# 1206_array.net
KiCad netlist of a schematic drawn in Altium Designer
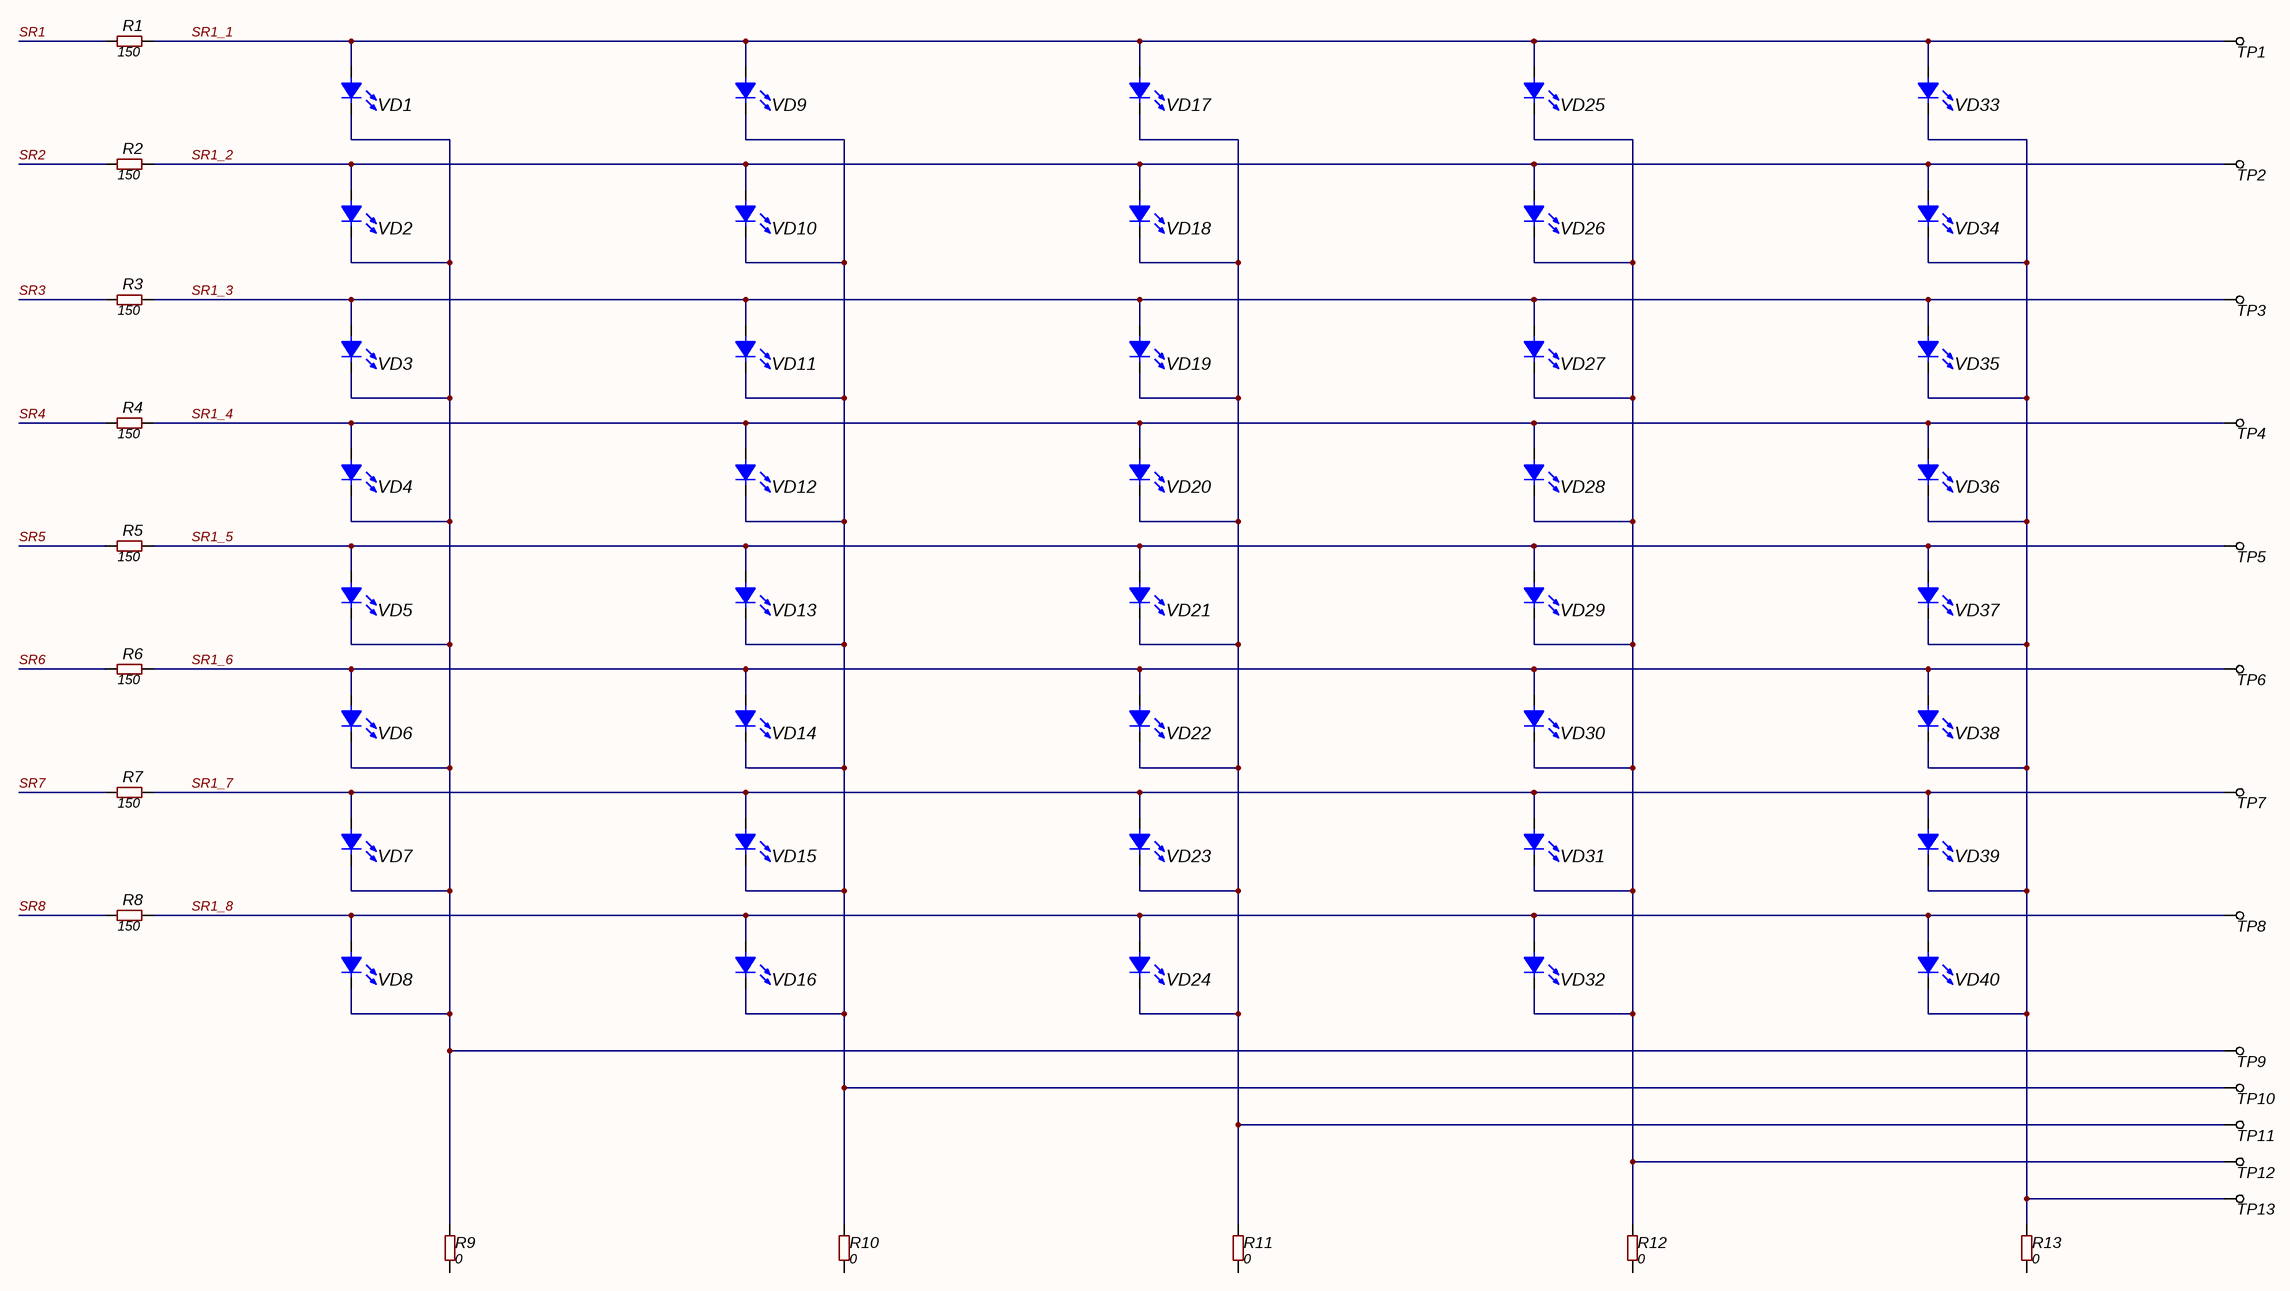
[diagram p0: 1206_array.SchDoc]

(export (version "E")
  (design (tool "Eeschema 10.0.6"))
  (components
    (comp (ref "R1")
      (value "150")
      (footprint "RES: 0603")
      (fields
        (field (name "MANUFACTURER") "Yageo")
        (field (name "PARTNUMBER") "RC0603JR-07100RL")
        (field (name "VALUEMANUFACTURERPARTNUMBER") "Resistor film, 150, , 0603, 0.1W, -55...+125°C")
      )
      (libsource (lib "") (part "Resistor_0603_1"))
    )
    (comp (ref "R2")
      (value "150")
      (footprint "RES: 0603")
      (fields
        (field (name "MANUFACTURER") "Yageo")
        (field (name "PARTNUMBER") "RC0603JR-07100RL")
        (field (name "VALUEMANUFACTURERPARTNUMBER") "Resistor film, 150, , 0603, 0.1W, -55...+125°C")
      )
      (libsource (lib "") (part "Resistor_0603_1"))
    )
    (comp (ref "R3")
      (value "150")
      (footprint "RES: 0603")
      (fields
        (field (name "MANUFACTURER") "Yageo")
        (field (name "PARTNUMBER") "RC0603JR-07100RL")
        (field (name "VALUEMANUFACTURERPARTNUMBER") "Resistor film, 150, , 0603, 0.1W, -55...+125°C")
      )
      (libsource (lib "") (part "Resistor_0603_1"))
    )
    (comp (ref "R4")
      (value "150")
      (footprint "RES: 0603")
      (fields
        (field (name "MANUFACTURER") "Yageo")
        (field (name "PARTNUMBER") "RC0603JR-07100RL")
        (field (name "VALUEMANUFACTURERPARTNUMBER") "Resistor film, 150, , 0603, 0.1W, -55...+125°C")
      )
      (libsource (lib "") (part "Resistor_0603_1"))
    )
    (comp (ref "R5")
      (value "150")
      (footprint "RES: 0603")
      (fields
        (field (name "MANUFACTURER") "Yageo")
        (field (name "PARTNUMBER") "RC0603JR-07100RL")
        (field (name "VALUEMANUFACTURERPARTNUMBER") "Resistor film, 150, , 0603, 0.1W, -55...+125°C")
      )
      (libsource (lib "") (part "Resistor_0603_1"))
    )
    (comp (ref "R6")
      (value "150")
      (footprint "RES: 0603")
      (fields
        (field (name "MANUFACTURER") "Yageo")
        (field (name "PARTNUMBER") "RC0603JR-07100RL")
        (field (name "VALUEMANUFACTURERPARTNUMBER") "Resistor film, 150, , 0603, 0.1W, -55...+125°C")
      )
      (libsource (lib "") (part "Resistor_0603_1"))
    )
    (comp (ref "R7")
      (value "150")
      (footprint "RES: 0603")
      (fields
        (field (name "MANUFACTURER") "Yageo")
        (field (name "PARTNUMBER") "RC0603JR-07100RL")
        (field (name "VALUEMANUFACTURERPARTNUMBER") "Resistor film, 150, , 0603, 0.1W, -55...+125°C")
      )
      (libsource (lib "") (part "Resistor_0603_1"))
    )
    (comp (ref "R8")
      (value "150")
      (footprint "RES: 0603")
      (fields
        (field (name "MANUFACTURER") "Yageo")
        (field (name "PARTNUMBER") "RC0603JR-07100RL")
        (field (name "VALUEMANUFACTURERPARTNUMBER") "Resistor film, 150, , 0603, 0.1W, -55...+125°C")
      )
      (libsource (lib "") (part "Resistor_0603_1"))
    )
    (comp (ref "R9")
      (value "0")
      (footprint "RES: 0603")
      (fields
        (field (name "MANUFACTURER") "Yageo")
        (field (name "PARTNUMBER") "RC0603JR-07100RL")
        (field (name "VALUEMANUFACTURERPARTNUMBER") "Resistor film, 0, , 0603, 0.1W, -55...+125°C")
      )
      (libsource (lib "resistor") (part "Resistor_0603"))
    )
    (comp (ref "R10")
      (value "0")
      (footprint "RES: 0603")
      (fields
        (field (name "MANUFACTURER") "Yageo")
        (field (name "PARTNUMBER") "RC0603JR-07100RL")
        (field (name "VALUEMANUFACTURERPARTNUMBER") "Resistor film, 0, , 0603, 0.1W, -55...+125°C")
      )
      (libsource (lib "resistor") (part "Resistor_0603"))
    )
    (comp (ref "R11")
      (value "0")
      (footprint "RES: 0603")
      (fields
        (field (name "MANUFACTURER") "Yageo")
        (field (name "PARTNUMBER") "RC0603JR-07100RL")
        (field (name "VALUEMANUFACTURERPARTNUMBER") "Resistor film, 0, , 0603, 0.1W, -55...+125°C")
      )
      (libsource (lib "resistor") (part "Resistor_0603"))
    )
    (comp (ref "R12")
      (value "0")
      (footprint "RES: 0603")
      (fields
        (field (name "MANUFACTURER") "Yageo")
        (field (name "PARTNUMBER") "RC0603JR-07100RL")
        (field (name "VALUEMANUFACTURERPARTNUMBER") "Resistor film, 0, , 0603, 0.1W, -55...+125°C")
      )
      (libsource (lib "resistor") (part "Resistor_0603"))
    )
    (comp (ref "R13")
      (value "0")
      (footprint "RES: 0603")
      (fields
        (field (name "MANUFACTURER") "Yageo")
        (field (name "PARTNUMBER") "RC0603JR-07100RL")
        (field (name "VALUEMANUFACTURERPARTNUMBER") "Resistor film, 0, , 0603, 0.1W, -55...+125°C")
      )
      (libsource (lib "resistor") (part "Resistor_0603"))
    )
    (comp (ref "TP1")
      (value "Testpoint_HS1mm")
      (footprint "TestPoint(without 3D)")
      (libsource (lib "connector") (part "Testpoint_HS1mm"))
    )
    (comp (ref "TP2")
      (value "Testpoint_HS1mm")
      (footprint "TestPoint(without 3D)")
      (libsource (lib "connector") (part "Testpoint_HS1mm"))
    )
    (comp (ref "TP3")
      (value "Testpoint_HS1mm")
      (footprint "TestPoint(without 3D)")
      (libsource (lib "connector") (part "Testpoint_HS1mm"))
    )
    (comp (ref "TP4")
      (value "Testpoint_HS1mm")
      (footprint "TestPoint(without 3D)")
      (libsource (lib "connector") (part "Testpoint_HS1mm"))
    )
    (comp (ref "TP5")
      (value "Testpoint_HS1mm")
      (footprint "TestPoint(without 3D)")
      (libsource (lib "connector") (part "Testpoint_HS1mm"))
    )
    (comp (ref "TP6")
      (value "Testpoint_HS1mm")
      (footprint "TestPoint(without 3D)")
      (libsource (lib "connector") (part "Testpoint_HS1mm"))
    )
    (comp (ref "TP7")
      (value "Testpoint_HS1mm")
      (footprint "TestPoint(without 3D)")
      (libsource (lib "connector") (part "Testpoint_HS1mm"))
    )
    (comp (ref "TP8")
      (value "Testpoint_HS1mm")
      (footprint "TestPoint(without 3D)")
      (libsource (lib "connector") (part "Testpoint_HS1mm"))
    )
    (comp (ref "TP9")
      (value "Testpoint_HS1mm")
      (footprint "TestPoint(without 3D)")
      (libsource (lib "connector") (part "Testpoint_HS1mm"))
    )
    (comp (ref "TP10")
      (value "Testpoint_HS1mm")
      (footprint "TestPoint(without 3D)")
      (libsource (lib "connector") (part "Testpoint_HS1mm"))
    )
    (comp (ref "TP11")
      (value "Testpoint_HS1mm")
      (footprint "TestPoint(without 3D)")
      (libsource (lib "connector") (part "Testpoint_HS1mm"))
    )
    (comp (ref "TP12")
      (value "Testpoint_HS1mm")
      (footprint "TestPoint(without 3D)")
      (libsource (lib "connector") (part "Testpoint_HS1mm"))
    )
    (comp (ref "TP13")
      (value "Testpoint_HS1mm")
      (footprint "TestPoint(without 3D)")
      (libsource (lib "connector") (part "Testpoint_HS1mm"))
    )
    (comp (ref "VD1")
      (value "~")
      (footprint "LED: 1206Y")
      (fields (field (name "VALUEMANUFACTURERPARTNUMBER") "LED, Green, *, *, *, -55...+150°C"))
      (libsource (lib "diode") (part "LED_single"))
    )
    (comp (ref "VD2")
      (value "~")
      (footprint "LED: 1206Y")
      (fields (field (name "VALUEMANUFACTURERPARTNUMBER") "LED, Green, *, *, *, -55...+150°C"))
      (libsource (lib "diode") (part "LED_single"))
    )
    (comp (ref "VD3")
      (value "~")
      (footprint "LED: 1206Y")
      (fields (field (name "VALUEMANUFACTURERPARTNUMBER") "LED, Green, *, *, *, -55...+150°C"))
      (libsource (lib "diode") (part "LED_single"))
    )
    (comp (ref "VD4")
      (value "~")
      (footprint "LED: 1206Y")
      (fields (field (name "VALUEMANUFACTURERPARTNUMBER") "LED, Green, *, *, *, -55...+150°C"))
      (libsource (lib "diode") (part "LED_single"))
    )
    (comp (ref "VD5")
      (value "~")
      (footprint "LED: 1206Y")
      (fields (field (name "VALUEMANUFACTURERPARTNUMBER") "LED, Green, *, *, *, -55...+150°C"))
      (libsource (lib "diode") (part "LED_single"))
    )
    (comp (ref "VD6")
      (value "~")
      (footprint "LED: 1206Y")
      (fields (field (name "VALUEMANUFACTURERPARTNUMBER") "LED, Green, *, *, *, -55...+150°C"))
      (libsource (lib "diode") (part "LED_single"))
    )
    (comp (ref "VD7")
      (value "~")
      (footprint "LED: 1206Y")
      (fields (field (name "VALUEMANUFACTURERPARTNUMBER") "LED, Green, *, *, *, -55...+150°C"))
      (libsource (lib "diode") (part "LED_single"))
    )
    (comp (ref "VD8")
      (value "~")
      (footprint "LED: 1206Y")
      (fields (field (name "VALUEMANUFACTURERPARTNUMBER") "LED, Green, *, *, *, -55...+150°C"))
      (libsource (lib "diode") (part "LED_single"))
    )
    (comp (ref "VD9")
      (value "~")
      (footprint "LED: 1206Y")
      (fields (field (name "VALUEMANUFACTURERPARTNUMBER") "LED, Green, *, *, *, -55...+150°C"))
      (libsource (lib "diode") (part "LED_single"))
    )
    (comp (ref "VD10")
      (value "~")
      (footprint "LED: 1206Y")
      (fields (field (name "VALUEMANUFACTURERPARTNUMBER") "LED, Green, *, *, *, -55...+150°C"))
      (libsource (lib "diode") (part "LED_single"))
    )
    (comp (ref "VD11")
      (value "~")
      (footprint "LED: 1206Y")
      (fields (field (name "VALUEMANUFACTURERPARTNUMBER") "LED, Green, *, *, *, -55...+150°C"))
      (libsource (lib "diode") (part "LED_single"))
    )
    (comp (ref "VD12")
      (value "~")
      (footprint "LED: 1206Y")
      (fields (field (name "VALUEMANUFACTURERPARTNUMBER") "LED, Green, *, *, *, -55...+150°C"))
      (libsource (lib "diode") (part "LED_single"))
    )
    (comp (ref "VD13")
      (value "~")
      (footprint "LED: 1206Y")
      (fields (field (name "VALUEMANUFACTURERPARTNUMBER") "LED, Green, *, *, *, -55...+150°C"))
      (libsource (lib "diode") (part "LED_single"))
    )
    (comp (ref "VD14")
      (value "~")
      (footprint "LED: 1206Y")
      (fields (field (name "VALUEMANUFACTURERPARTNUMBER") "LED, Green, *, *, *, -55...+150°C"))
      (libsource (lib "diode") (part "LED_single"))
    )
    (comp (ref "VD15")
      (value "~")
      (footprint "LED: 1206Y")
      (fields (field (name "VALUEMANUFACTURERPARTNUMBER") "LED, Green, *, *, *, -55...+150°C"))
      (libsource (lib "diode") (part "LED_single"))
    )
    (comp (ref "VD16")
      (value "~")
      (footprint "LED: 1206Y")
      (fields (field (name "VALUEMANUFACTURERPARTNUMBER") "LED, Green, *, *, *, -55...+150°C"))
      (libsource (lib "diode") (part "LED_single"))
    )
    (comp (ref "VD17")
      (value "~")
      (footprint "LED: 1206Y")
      (fields (field (name "VALUEMANUFACTURERPARTNUMBER") "LED, Green, *, *, *, -55...+150°C"))
      (libsource (lib "diode") (part "LED_single"))
    )
    (comp (ref "VD18")
      (value "~")
      (footprint "LED: 1206Y")
      (fields (field (name "VALUEMANUFACTURERPARTNUMBER") "LED, Green, *, *, *, -55...+150°C"))
      (libsource (lib "diode") (part "LED_single"))
    )
    (comp (ref "VD19")
      (value "~")
      (footprint "LED: 1206Y")
      (fields (field (name "VALUEMANUFACTURERPARTNUMBER") "LED, Green, *, *, *, -55...+150°C"))
      (libsource (lib "diode") (part "LED_single"))
    )
    (comp (ref "VD20")
      (value "~")
      (footprint "LED: 1206Y")
      (fields (field (name "VALUEMANUFACTURERPARTNUMBER") "LED, Green, *, *, *, -55...+150°C"))
      (libsource (lib "diode") (part "LED_single"))
    )
    (comp (ref "VD21")
      (value "~")
      (footprint "LED: 1206Y")
      (fields (field (name "VALUEMANUFACTURERPARTNUMBER") "LED, Green, *, *, *, -55...+150°C"))
      (libsource (lib "diode") (part "LED_single"))
    )
    (comp (ref "VD22")
      (value "~")
      (footprint "LED: 1206Y")
      (fields (field (name "VALUEMANUFACTURERPARTNUMBER") "LED, Green, *, *, *, -55...+150°C"))
      (libsource (lib "diode") (part "LED_single"))
    )
    (comp (ref "VD23")
      (value "~")
      (footprint "LED: 1206Y")
      (fields (field (name "VALUEMANUFACTURERPARTNUMBER") "LED, Green, *, *, *, -55...+150°C"))
      (libsource (lib "diode") (part "LED_single"))
    )
    (comp (ref "VD24")
      (value "~")
      (footprint "LED: 1206Y")
      (fields (field (name "VALUEMANUFACTURERPARTNUMBER") "LED, Green, *, *, *, -55...+150°C"))
      (libsource (lib "diode") (part "LED_single"))
    )
    (comp (ref "VD25")
      (value "~")
      (footprint "LED: 1206Y")
      (fields (field (name "VALUEMANUFACTURERPARTNUMBER") "LED, Green, *, *, *, -55...+150°C"))
      (libsource (lib "diode") (part "LED_single"))
    )
    (comp (ref "VD26")
      (value "~")
      (footprint "LED: 1206Y")
      (fields (field (name "VALUEMANUFACTURERPARTNUMBER") "LED, Green, *, *, *, -55...+150°C"))
      (libsource (lib "diode") (part "LED_single"))
    )
    (comp (ref "VD27")
      (value "~")
      (footprint "LED: 1206Y")
      (fields (field (name "VALUEMANUFACTURERPARTNUMBER") "LED, Green, *, *, *, -55...+150°C"))
      (libsource (lib "diode") (part "LED_single"))
    )
    (comp (ref "VD28")
      (value "~")
      (footprint "LED: 1206Y")
      (fields (field (name "VALUEMANUFACTURERPARTNUMBER") "LED, Green, *, *, *, -55...+150°C"))
      (libsource (lib "diode") (part "LED_single"))
    )
    (comp (ref "VD29")
      (value "~")
      (footprint "LED: 1206Y")
      (fields (field (name "VALUEMANUFACTURERPARTNUMBER") "LED, Green, *, *, *, -55...+150°C"))
      (libsource (lib "diode") (part "LED_single"))
    )
    (comp (ref "VD30")
      (value "~")
      (footprint "LED: 1206Y")
      (fields (field (name "VALUEMANUFACTURERPARTNUMBER") "LED, Green, *, *, *, -55...+150°C"))
      (libsource (lib "diode") (part "LED_single"))
    )
    (comp (ref "VD31")
      (value "~")
      (footprint "LED: 1206Y")
      (fields (field (name "VALUEMANUFACTURERPARTNUMBER") "LED, Green, *, *, *, -55...+150°C"))
      (libsource (lib "diode") (part "LED_single"))
    )
    (comp (ref "VD32")
      (value "~")
      (footprint "LED: 1206Y")
      (fields (field (name "VALUEMANUFACTURERPARTNUMBER") "LED, Green, *, *, *, -55...+150°C"))
      (libsource (lib "diode") (part "LED_single"))
    )
    (comp (ref "VD33")
      (value "~")
      (footprint "LED: 1206Y")
      (fields (field (name "VALUEMANUFACTURERPARTNUMBER") "LED, Green, *, *, *, -55...+150°C"))
      (libsource (lib "diode") (part "LED_single"))
    )
    (comp (ref "VD34")
      (value "~")
      (footprint "LED: 1206Y")
      (fields (field (name "VALUEMANUFACTURERPARTNUMBER") "LED, Green, *, *, *, -55...+150°C"))
      (libsource (lib "diode") (part "LED_single"))
    )
    (comp (ref "VD35")
      (value "~")
      (footprint "LED: 1206Y")
      (fields (field (name "VALUEMANUFACTURERPARTNUMBER") "LED, Green, *, *, *, -55...+150°C"))
      (libsource (lib "diode") (part "LED_single"))
    )
    (comp (ref "VD36")
      (value "~")
      (footprint "LED: 1206Y")
      (fields (field (name "VALUEMANUFACTURERPARTNUMBER") "LED, Green, *, *, *, -55...+150°C"))
      (libsource (lib "diode") (part "LED_single"))
    )
    (comp (ref "VD37")
      (value "~")
      (footprint "LED: 1206Y")
      (fields (field (name "VALUEMANUFACTURERPARTNUMBER") "LED, Green, *, *, *, -55...+150°C"))
      (libsource (lib "diode") (part "LED_single"))
    )
    (comp (ref "VD38")
      (value "~")
      (footprint "LED: 1206Y")
      (fields (field (name "VALUEMANUFACTURERPARTNUMBER") "LED, Green, *, *, *, -55...+150°C"))
      (libsource (lib "diode") (part "LED_single"))
    )
    (comp (ref "VD39")
      (value "~")
      (footprint "LED: 1206Y")
      (fields (field (name "VALUEMANUFACTURERPARTNUMBER") "LED, Green, *, *, *, -55...+150°C"))
      (libsource (lib "diode") (part "LED_single"))
    )
    (comp (ref "VD40")
      (value "~")
      (footprint "LED: 1206Y")
      (fields (field (name "VALUEMANUFACTURERPARTNUMBER") "LED, Green, *, *, *, -55...+150°C"))
      (libsource (lib "diode") (part "LED_single"))
    )
  )
  (nets
    (net (code "1") (name "/SR1") (class "Default")
      (node (ref "R1") (pin "1") (pinfunction "1_1") (pintype "passive"))
    )
    (net (code "2") (name "/SR1_1") (class "Default")
      (node (ref "R1") (pin "2") (pinfunction "2_2") (pintype "passive"))
      (node (ref "TP1") (pin "1") (pinfunction "1_1") (pintype "passive"))
      (node (ref "VD1") (pin "1") (pinfunction "A_1") (pintype "passive"))
      (node (ref "VD17") (pin "1") (pinfunction "A_1") (pintype "passive"))
      (node (ref "VD25") (pin "1") (pinfunction "A_1") (pintype "passive"))
      (node (ref "VD33") (pin "1") (pinfunction "A_1") (pintype "passive"))
      (node (ref "VD9") (pin "1") (pinfunction "A_1") (pintype "passive"))
    )
    (net (code "3") (name "/SR1_2") (class "Default")
      (node (ref "R2") (pin "2") (pinfunction "2_2") (pintype "passive"))
      (node (ref "TP2") (pin "1") (pinfunction "1_1") (pintype "passive"))
      (node (ref "VD10") (pin "1") (pinfunction "A_1") (pintype "passive"))
      (node (ref "VD18") (pin "1") (pinfunction "A_1") (pintype "passive"))
      (node (ref "VD2") (pin "1") (pinfunction "A_1") (pintype "passive"))
      (node (ref "VD26") (pin "1") (pinfunction "A_1") (pintype "passive"))
      (node (ref "VD34") (pin "1") (pinfunction "A_1") (pintype "passive"))
    )
    (net (code "4") (name "/SR1_3") (class "Default")
      (node (ref "R3") (pin "2") (pinfunction "2_2") (pintype "passive"))
      (node (ref "TP3") (pin "1") (pinfunction "1_1") (pintype "passive"))
      (node (ref "VD11") (pin "1") (pinfunction "A_1") (pintype "passive"))
      (node (ref "VD19") (pin "1") (pinfunction "A_1") (pintype "passive"))
      (node (ref "VD27") (pin "1") (pinfunction "A_1") (pintype "passive"))
      (node (ref "VD3") (pin "1") (pinfunction "A_1") (pintype "passive"))
      (node (ref "VD35") (pin "1") (pinfunction "A_1") (pintype "passive"))
    )
    (net (code "5") (name "/SR1_4") (class "Default")
      (node (ref "R4") (pin "2") (pinfunction "2_2") (pintype "passive"))
      (node (ref "TP4") (pin "1") (pinfunction "1_1") (pintype "passive"))
      (node (ref "VD12") (pin "1") (pinfunction "A_1") (pintype "passive"))
      (node (ref "VD20") (pin "1") (pinfunction "A_1") (pintype "passive"))
      (node (ref "VD28") (pin "1") (pinfunction "A_1") (pintype "passive"))
      (node (ref "VD36") (pin "1") (pinfunction "A_1") (pintype "passive"))
      (node (ref "VD4") (pin "1") (pinfunction "A_1") (pintype "passive"))
    )
    (net (code "6") (name "/SR1_5") (class "Default")
      (node (ref "R5") (pin "2") (pinfunction "2_2") (pintype "passive"))
      (node (ref "TP5") (pin "1") (pinfunction "1_1") (pintype "passive"))
      (node (ref "VD13") (pin "1") (pinfunction "A_1") (pintype "passive"))
      (node (ref "VD21") (pin "1") (pinfunction "A_1") (pintype "passive"))
      (node (ref "VD29") (pin "1") (pinfunction "A_1") (pintype "passive"))
      (node (ref "VD37") (pin "1") (pinfunction "A_1") (pintype "passive"))
      (node (ref "VD5") (pin "1") (pinfunction "A_1") (pintype "passive"))
    )
    (net (code "7") (name "/SR1_6") (class "Default")
      (node (ref "R6") (pin "2") (pinfunction "2_2") (pintype "passive"))
      (node (ref "TP6") (pin "1") (pinfunction "1_1") (pintype "passive"))
      (node (ref "VD14") (pin "1") (pinfunction "A_1") (pintype "passive"))
      (node (ref "VD22") (pin "1") (pinfunction "A_1") (pintype "passive"))
      (node (ref "VD30") (pin "1") (pinfunction "A_1") (pintype "passive"))
      (node (ref "VD38") (pin "1") (pinfunction "A_1") (pintype "passive"))
      (node (ref "VD6") (pin "1") (pinfunction "A_1") (pintype "passive"))
    )
    (net (code "8") (name "/SR1_7") (class "Default")
      (node (ref "R7") (pin "2") (pinfunction "2_2") (pintype "passive"))
      (node (ref "TP7") (pin "1") (pinfunction "1_1") (pintype "passive"))
      (node (ref "VD15") (pin "1") (pinfunction "A_1") (pintype "passive"))
      (node (ref "VD23") (pin "1") (pinfunction "A_1") (pintype "passive"))
      (node (ref "VD31") (pin "1") (pinfunction "A_1") (pintype "passive"))
      (node (ref "VD39") (pin "1") (pinfunction "A_1") (pintype "passive"))
      (node (ref "VD7") (pin "1") (pinfunction "A_1") (pintype "passive"))
    )
    (net (code "9") (name "/SR1_8") (class "Default")
      (node (ref "R8") (pin "2") (pinfunction "2_2") (pintype "passive"))
      (node (ref "TP8") (pin "1") (pinfunction "1_1") (pintype "passive"))
      (node (ref "VD16") (pin "1") (pinfunction "A_1") (pintype "passive"))
      (node (ref "VD24") (pin "1") (pinfunction "A_1") (pintype "passive"))
      (node (ref "VD32") (pin "1") (pinfunction "A_1") (pintype "passive"))
      (node (ref "VD40") (pin "1") (pinfunction "A_1") (pintype "passive"))
      (node (ref "VD8") (pin "1") (pinfunction "A_1") (pintype "passive"))
    )
    (net (code "10") (name "/SR2") (class "Default")
      (node (ref "R2") (pin "1") (pinfunction "1_1") (pintype "passive"))
    )
    (net (code "11") (name "/SR3") (class "Default")
      (node (ref "R3") (pin "1") (pinfunction "1_1") (pintype "passive"))
    )
    (net (code "12") (name "/SR4") (class "Default")
      (node (ref "R4") (pin "1") (pinfunction "1_1") (pintype "passive"))
    )
    (net (code "13") (name "/SR5") (class "Default")
      (node (ref "R5") (pin "1") (pinfunction "1_1") (pintype "passive"))
    )
    (net (code "14") (name "/SR6") (class "Default")
      (node (ref "R6") (pin "1") (pinfunction "1_1") (pintype "passive"))
    )
    (net (code "15") (name "/SR7") (class "Default")
      (node (ref "R7") (pin "1") (pinfunction "1_1") (pintype "passive"))
    )
    (net (code "16") (name "/SR8") (class "Default")
      (node (ref "R8") (pin "1") (pinfunction "1_1") (pintype "passive"))
    )
    (net (code "17") (name "Net-(VD1-C)") (class "Default")
      (node (ref "R9") (pin "2") (pinfunction "2_2") (pintype "passive"))
      (node (ref "TP9") (pin "1") (pinfunction "1_1") (pintype "passive"))
      (node (ref "VD1") (pin "2") (pinfunction "C_2") (pintype "passive"))
      (node (ref "VD2") (pin "2") (pinfunction "C_2") (pintype "passive"))
      (node (ref "VD3") (pin "2") (pinfunction "C_2") (pintype "passive"))
      (node (ref "VD4") (pin "2") (pinfunction "C_2") (pintype "passive"))
      (node (ref "VD5") (pin "2") (pinfunction "C_2") (pintype "passive"))
      (node (ref "VD6") (pin "2") (pinfunction "C_2") (pintype "passive"))
      (node (ref "VD7") (pin "2") (pinfunction "C_2") (pintype "passive"))
      (node (ref "VD8") (pin "2") (pinfunction "C_2") (pintype "passive"))
    )
    (net (code "18") (name "Net-(VD10-C)") (class "Default")
      (node (ref "R10") (pin "2") (pinfunction "2_2") (pintype "passive"))
      (node (ref "TP10") (pin "1") (pinfunction "1_1") (pintype "passive"))
      (node (ref "VD10") (pin "2") (pinfunction "C_2") (pintype "passive"))
      (node (ref "VD11") (pin "2") (pinfunction "C_2") (pintype "passive"))
      (node (ref "VD12") (pin "2") (pinfunction "C_2") (pintype "passive"))
      (node (ref "VD13") (pin "2") (pinfunction "C_2") (pintype "passive"))
      (node (ref "VD14") (pin "2") (pinfunction "C_2") (pintype "passive"))
      (node (ref "VD15") (pin "2") (pinfunction "C_2") (pintype "passive"))
      (node (ref "VD16") (pin "2") (pinfunction "C_2") (pintype "passive"))
      (node (ref "VD9") (pin "2") (pinfunction "C_2") (pintype "passive"))
    )
    (net (code "19") (name "Net-(VD17-C)") (class "Default")
      (node (ref "R11") (pin "2") (pinfunction "2_2") (pintype "passive"))
      (node (ref "TP11") (pin "1") (pinfunction "1_1") (pintype "passive"))
      (node (ref "VD17") (pin "2") (pinfunction "C_2") (pintype "passive"))
      (node (ref "VD18") (pin "2") (pinfunction "C_2") (pintype "passive"))
      (node (ref "VD19") (pin "2") (pinfunction "C_2") (pintype "passive"))
      (node (ref "VD20") (pin "2") (pinfunction "C_2") (pintype "passive"))
      (node (ref "VD21") (pin "2") (pinfunction "C_2") (pintype "passive"))
      (node (ref "VD22") (pin "2") (pinfunction "C_2") (pintype "passive"))
      (node (ref "VD23") (pin "2") (pinfunction "C_2") (pintype "passive"))
      (node (ref "VD24") (pin "2") (pinfunction "C_2") (pintype "passive"))
    )
    (net (code "20") (name "Net-(VD25-C)") (class "Default")
      (node (ref "R12") (pin "2") (pinfunction "2_2") (pintype "passive"))
      (node (ref "TP12") (pin "1") (pinfunction "1_1") (pintype "passive"))
      (node (ref "VD25") (pin "2") (pinfunction "C_2") (pintype "passive"))
      (node (ref "VD26") (pin "2") (pinfunction "C_2") (pintype "passive"))
      (node (ref "VD27") (pin "2") (pinfunction "C_2") (pintype "passive"))
      (node (ref "VD28") (pin "2") (pinfunction "C_2") (pintype "passive"))
      (node (ref "VD29") (pin "2") (pinfunction "C_2") (pintype "passive"))
      (node (ref "VD30") (pin "2") (pinfunction "C_2") (pintype "passive"))
      (node (ref "VD31") (pin "2") (pinfunction "C_2") (pintype "passive"))
      (node (ref "VD32") (pin "2") (pinfunction "C_2") (pintype "passive"))
    )
    (net (code "21") (name "Net-(VD33-C)") (class "Default")
      (node (ref "R13") (pin "2") (pinfunction "2_2") (pintype "passive"))
      (node (ref "TP13") (pin "1") (pinfunction "1_1") (pintype "passive"))
      (node (ref "VD33") (pin "2") (pinfunction "C_2") (pintype "passive"))
      (node (ref "VD34") (pin "2") (pinfunction "C_2") (pintype "passive"))
      (node (ref "VD35") (pin "2") (pinfunction "C_2") (pintype "passive"))
      (node (ref "VD36") (pin "2") (pinfunction "C_2") (pintype "passive"))
      (node (ref "VD37") (pin "2") (pinfunction "C_2") (pintype "passive"))
      (node (ref "VD38") (pin "2") (pinfunction "C_2") (pintype "passive"))
      (node (ref "VD39") (pin "2") (pinfunction "C_2") (pintype "passive"))
      (node (ref "VD40") (pin "2") (pinfunction "C_2") (pintype "passive"))
    )
    (net (code "22") (name "unconnected-(R9-Pad1)") (class "Default")
      (node (ref "R9") (pin "1") (pinfunction "1_1") (pintype "passive"))
    )
    (net (code "23") (name "unconnected-(R10-Pad1)") (class "Default")
      (node (ref "R10") (pin "1") (pinfunction "1_1") (pintype "passive"))
    )
    (net (code "24") (name "unconnected-(R11-Pad1)") (class "Default")
      (node (ref "R11") (pin "1") (pinfunction "1_1") (pintype "passive"))
    )
    (net (code "25") (name "unconnected-(R12-Pad1)") (class "Default")
      (node (ref "R12") (pin "1") (pinfunction "1_1") (pintype "passive"))
    )
    (net (code "26") (name "unconnected-(R13-Pad1)") (class "Default")
      (node (ref "R13") (pin "1") (pinfunction "1_1") (pintype "passive"))
    )
  )
)
